# Power_Regulators_Digital_1.net
KiCad netlist of a schematic drawn in Altium Designer
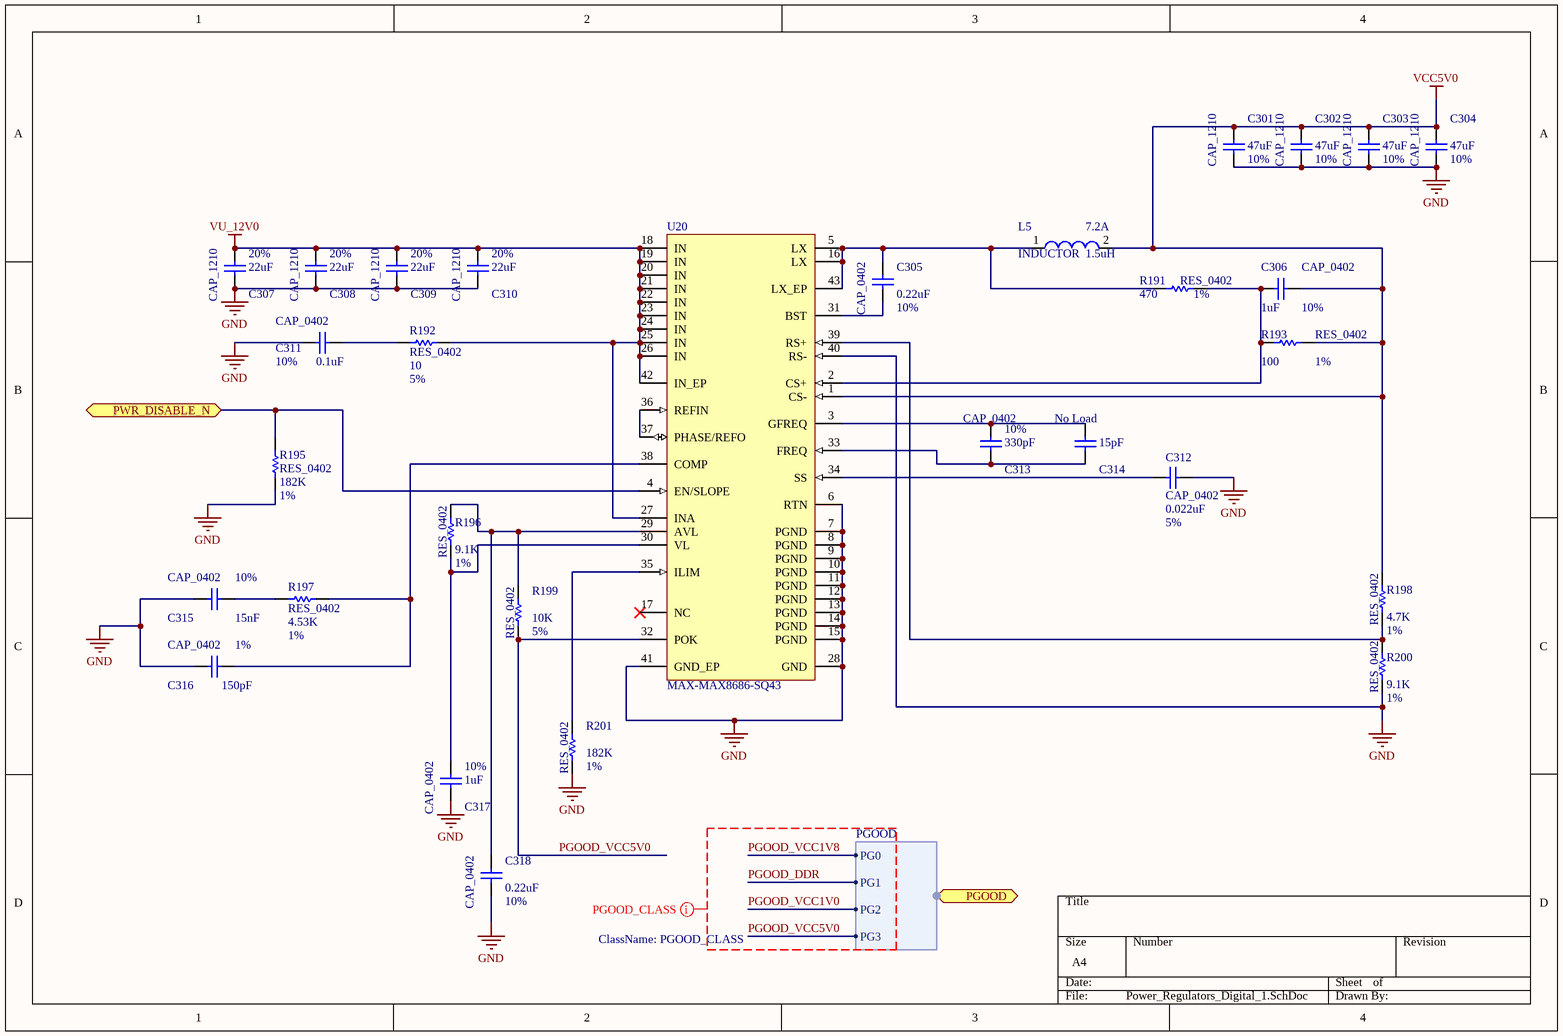
[diagram p0: Power_Regulators_Digital_1.SchDoc]

(export (version "E")
  (design (tool "Eeschema 10.0.6"))
  (components
    (comp (ref "C301")
      (value "CAP_1210")
      (footprint "CAPC1210(3225)100_N")
      (description "47uF, ceramic, 10% 10V X7R, 1210")
      (fields
        (field (name "ALTIUM_VALUE") "47uF")
        (field (name "TOLERANCE") "10%")
        (field (name "PART NUMBER") "GRM32ER71A476KE15L")
        (field (name "MANUFACTURER") "Murata Electronics North America")
      )
      (libsource (lib "COMRAD_Database") (part "CAP_1210"))
    )
    (comp (ref "C302")
      (value "CAP_1210")
      (footprint "CAPC1210(3225)100_N")
      (description "47uF, ceramic, 10% 10V X7R, 1210")
      (fields
        (field (name "ALTIUM_VALUE") "47uF")
        (field (name "TOLERANCE") "10%")
        (field (name "PART NUMBER") "GRM32ER71A476KE15L")
        (field (name "MANUFACTURER") "Murata Electronics North America")
      )
      (libsource (lib "COMRAD_Database") (part "CAP_1210"))
    )
    (comp (ref "C303")
      (value "CAP_1210")
      (footprint "CAPC1210(3225)100_N")
      (description "47uF, ceramic, 10% 10V X7R, 1210")
      (fields
        (field (name "ALTIUM_VALUE") "47uF")
        (field (name "TOLERANCE") "10%")
        (field (name "PART NUMBER") "GRM32ER71A476KE15L")
        (field (name "MANUFACTURER") "Murata Electronics North America")
      )
      (libsource (lib "COMRAD_Database") (part "CAP_1210"))
    )
    (comp (ref "C304")
      (value "CAP_1210")
      (footprint "CAPC1210(3225)100_N")
      (description "47uF, ceramic, 10% 10V X7R, 1210")
      (fields
        (field (name "ALTIUM_VALUE") "47uF")
        (field (name "TOLERANCE") "10%")
        (field (name "PART NUMBER") "GRM32ER71A476KE15L")
        (field (name "MANUFACTURER") "Murata Electronics North America")
      )
      (libsource (lib "COMRAD_Database") (part "CAP_1210"))
    )
    (comp (ref "C305")
      (value "CAP_0402")
      (footprint "CAPC0402(1005)60_N")
      (description "0.22uF, ceramic, 10%, 6.3V X5R, 0402")
      (fields
        (field (name "ALTIUM_VALUE") "0.22uF")
        (field (name "TOLERANCE") "10%")
        (field (name "PART NUMBER") "04026D224KAT2A")
        (field (name "MANUFACTURER") "AVX Corporation")
      )
      (libsource (lib "COMRAD_Database") (part "CAP_0402"))
    )
    (comp (ref "C306")
      (value "CAP_0402")
      (footprint "CAPC0402(1005)60_N")
      (description "1uF, ceramic, 10%, 6.3V, X5R, 0402")
      (fields
        (field (name "ALTIUM_VALUE") "1uF")
        (field (name "TOLERANCE") "10%")
        (field (name "PART NUMBER") "C1005X5R0J105K")
        (field (name "MANUFACTURER") "TDK Corporation")
      )
      (libsource (lib "COMRAD_Database") (part "CAP_0402"))
    )
    (comp (ref "C307")
      (value "CAP_1210")
      (footprint "CAPC1210(3225)100_N")
      (description "22uF, ceramic, 20% 25V X7R, 1210")
      (fields
        (field (name "ALTIUM_VALUE") "22uF")
        (field (name "TOLERANCE") "20%")
        (field (name "PART NUMBER") "C1210C226M3RACTU")
        (field (name "MANUFACTURER") "Kemet")
      )
      (libsource (lib "COMRAD_Database") (part "CAP_1210"))
    )
    (comp (ref "C308")
      (value "CAP_1210")
      (footprint "CAPC1210(3225)100_N")
      (description "22uF, ceramic, 20% 25V X7R, 1210")
      (fields
        (field (name "ALTIUM_VALUE") "22uF")
        (field (name "TOLERANCE") "20%")
        (field (name "PART NUMBER") "C1210C226M3RACTU")
        (field (name "MANUFACTURER") "Kemet")
      )
      (libsource (lib "COMRAD_Database") (part "CAP_1210"))
    )
    (comp (ref "C309")
      (value "CAP_1210")
      (footprint "CAPC1210(3225)100_N")
      (description "22uF, ceramic, 20% 25V X7R, 1210")
      (fields
        (field (name "ALTIUM_VALUE") "22uF")
        (field (name "TOLERANCE") "20%")
        (field (name "PART NUMBER") "C1210C226M3RACTU")
        (field (name "MANUFACTURER") "Kemet")
      )
      (libsource (lib "COMRAD_Database") (part "CAP_1210"))
    )
    (comp (ref "C310")
      (value "CAP_1210")
      (footprint "CAPC1210(3225)100_N")
      (description "22uF, ceramic, 20% 25V X7R, 1210")
      (fields
        (field (name "ALTIUM_VALUE") "22uF")
        (field (name "TOLERANCE") "20%")
        (field (name "PART NUMBER") "C1210C226M3RACTU")
        (field (name "MANUFACTURER") "Kemet")
      )
      (libsource (lib "COMRAD_Database") (part "CAP_1210"))
    )
    (comp (ref "C311")
      (value "CAP_0402")
      (footprint "CAPC0402(1005)60_N")
      (description "0.1uF, ceramic, 10%, 25V, X5R, 0402")
      (fields
        (field (name "ALTIUM_VALUE") "0.1uF")
        (field (name "TOLERANCE") "10%")
        (field (name "PART NUMBER") "TMK105BJ104KV-F")
        (field (name "MANUFACTURER") "Taiyo Yuden")
      )
      (libsource (lib "COMRAD_Database") (part "CAP_0402"))
    )
    (comp (ref "C312")
      (value "CAP_0402")
      (footprint "CAPC0402(1005)60_N")
      (description "0.022uF, ceramic, 5% 16V X7R, 0402")
      (fields
        (field (name "ALTIUM_VALUE") "0.022uF")
        (field (name "TOLERANCE") "5%")
        (field (name "PART NUMBER") "0402YC223JAT2A")
        (field (name "MANUFACTURER") "AVX Corporation")
      )
      (libsource (lib "COMRAD_Database") (part "CAP_0402"))
    )
    (comp (ref "C313")
      (value "CAP_0402")
      (footprint "CAPC0402(1005)60_N")
      (description "330pF, ceramic, 10% 10V X7R, 0402")
      (fields
        (field (name "ALTIUM_VALUE") "330pF")
        (field (name "TOLERANCE") "10%")
        (field (name "PART NUMBER") "0402ZC331KAT2A")
        (field (name "MANUFACTURER") "AVX Corporation")
      )
      (libsource (lib "COMRAD_Database") (part "CAP_0402"))
    )
    (comp (ref "C314")
      (value "15pF")
      (footprint "CAPC0201(0603)33_N:CAPC0201(0603)33_N")
      (description "Generic Capacitor")
      (fields
        (field (name "PART NUMBER") "No Load_15pF")
        (field (name "MANUFACTURER") "No Load")
        (field (name "Comment") "CAP_0201")
      )
      (libsource (lib "COMRAD_Database") (part "CAP_0201"))
    )
    (comp (ref "C315")
      (value "CAP_0402")
      (footprint "CAPC0402(1005)60_N")
      (description "0.015uF, ceramic, 10% 6.3V X5R, 0402")
      (fields
        (field (name "ALTIUM_VALUE") "15nF")
        (field (name "TOLERANCE") "10%")
        (field (name "PART NUMBER") "C0402C153K9PACTU")
        (field (name "MANUFACTURER") "Kemet")
      )
      (libsource (lib "COMRAD_Database") (part "CAP_0402"))
    )
    (comp (ref "C316")
      (value "CAP_0402")
      (footprint "CAPC0402(1005)60_N")
      (description "150pF, ceramic, 1% 50V NP0, 0402")
      (fields
        (field (name "ALTIUM_VALUE") "150pF")
        (field (name "TOLERANCE") "1%")
        (field (name "PART NUMBER") "C1005C0G1H151F")
        (field (name "MANUFACTURER") "TDK Corporation")
      )
      (libsource (lib "COMRAD_Database") (part "CAP_0402"))
    )
    (comp (ref "C317")
      (value "CAP_0402")
      (footprint "CAPC0402(1005)60_N")
      (description "1uF, ceramic, 10%, 6.3V, X5R, 0402")
      (fields
        (field (name "ALTIUM_VALUE") "1uF")
        (field (name "TOLERANCE") "10%")
        (field (name "PART NUMBER") "C1005X5R0J105K")
        (field (name "MANUFACTURER") "TDK Corporation")
      )
      (libsource (lib "COMRAD_Database") (part "CAP_0402"))
    )
    (comp (ref "C318")
      (value "CAP_0402")
      (footprint "CAPC0402(1005)60_N")
      (description "0.22uF, ceramic, 10%, 6.3V X5R, 0402")
      (fields
        (field (name "ALTIUM_VALUE") "0.22uF")
        (field (name "TOLERANCE") "10%")
        (field (name "PART NUMBER") "04026D224KAT2A")
        (field (name "MANUFACTURER") "AVX Corporation")
      )
      (libsource (lib "COMRAD_Database") (part "CAP_0402"))
    )
    (comp (ref "L5")
      (value "INDUCTOR")
      (footprint "Inductor_IHLP2020CZER1R5M01_2-PIN")
      (description "IHLP2020CZER1R5M01, 1.5uH 7.2A, SMD")
      (fields
        (field (name "ALTIUM_VALUE") "1.5uH")
        (field (name "CURRENT") "7.2A")
        (field (name "PART NUMBER") "IHLP2020CZER1R5M01")
        (field (name "MANUFACTURER") "Vishay/Dale")
      )
      (libsource (lib "COMRAD_Database") (part "SYM-0029-00001-1"))
    )
    (comp (ref "R191")
      (value "RES_0402")
      (footprint "RESC0402(1005)_N")
      (description "470 ohm, 1% 1/16W, 0402")
      (fields
        (field (name "ALTIUM_VALUE") "470")
        (field (name "TOLERANCE") "1%")
        (field (name "PART NUMBER") "RC0402FR-07470RL")
        (field (name "MANUFACTURER") "YAGEO")
      )
      (libsource (lib "COMRAD_Database") (part "RES_0402"))
    )
    (comp (ref "R192")
      (value "RES_0402")
      (footprint "RESC0402(1005)_N")
      (description "10 ohm, 5%, 1/16W, 0402")
      (fields
        (field (name "ALTIUM_VALUE") "10")
        (field (name "TOLERANCE") "5%")
        (field (name "PART NUMBER") "RC0402JR-0710RL")
        (field (name "MANUFACTURER") "Yageo America")
      )
      (libsource (lib "COMRAD_Database") (part "RES_0402"))
    )
    (comp (ref "R193")
      (value "RES_0402")
      (footprint "RESC0402(1005)_N")
      (description "100 ohm, 1%, 1/16W, 0402")
      (fields
        (field (name "ALTIUM_VALUE") "100")
        (field (name "TOLERANCE") "1%")
        (field (name "PART NUMBER") "MCR01MZPF1000")
        (field (name "MANUFACTURER") "ROHM")
      )
      (libsource (lib "COMRAD_Database") (part "RES_0402"))
    )
    (comp (ref "R195")
      (value "RES_0402")
      (footprint "RESC0402(1005)_N")
      (description "182K ohm, 1%, 1/16W, 0402")
      (fields
        (field (name "ALTIUM_VALUE") "182K")
        (field (name "TOLERANCE") "1%")
        (field (name "PART NUMBER") "ERJ-2RKF1823X")
        (field (name "MANUFACTURER") "Panasonic - ECG")
      )
      (libsource (lib "COMRAD_Database") (part "RES_0402"))
    )
    (comp (ref "R196")
      (value "RES_0402")
      (footprint "RESC0402(1005)_N")
      (description "9.1K ohm, 1% 1/10W, 0402")
      (fields
        (field (name "ALTIUM_VALUE") "9.1K")
        (field (name "TOLERANCE") "1%")
        (field (name "PART NUMBER") "ERJ-2RKF9101X")
        (field (name "MANUFACTURER") "Panasonic - ECG")
      )
      (libsource (lib "COMRAD_Database") (part "RES_0402"))
    )
    (comp (ref "R197")
      (value "RES_0402")
      (footprint "RESC0402(1005)_N")
      (description "4.53K ohm, 1%, 1/16W, 0402")
      (fields
        (field (name "ALTIUM_VALUE") "4.53K")
        (field (name "TOLERANCE") "1%")
        (field (name "PART NUMBER") "ERJ-2RKF4531X")
        (field (name "MANUFACTURER") "Panasonic - ECG")
      )
      (libsource (lib "COMRAD_Database") (part "RES_0402"))
    )
    (comp (ref "R198")
      (value "RES_0402")
      (footprint "RESC0402(1005)_N")
      (description "4.7K ohm, 1%, 1/16W, 0402")
      (fields
        (field (name "ALTIUM_VALUE") "4.7K")
        (field (name "TOLERANCE") "1%")
        (field (name "PART NUMBER") "RC0402FR-074K7L")
        (field (name "MANUFACTURER") "Yageo America")
      )
      (libsource (lib "COMRAD_Database") (part "RES_0402"))
    )
    (comp (ref "R199")
      (value "RES_0402")
      (footprint "RESC0402(1005)_N")
      (description "10K ohm, 5%, 1/16W, 0402")
      (fields
        (field (name "ALTIUM_VALUE") "10K")
        (field (name "TOLERANCE") "5%")
        (field (name "PART NUMBER") "RC0402JR-0710KL")
        (field (name "MANUFACTURER") "Yageo America")
      )
      (libsource (lib "COMRAD_Database") (part "RES_0402"))
    )
    (comp (ref "R200")
      (value "RES_0402")
      (footprint "RESC0402(1005)_N")
      (description "9.1K ohm, 1% 1/10W, 0402")
      (fields
        (field (name "ALTIUM_VALUE") "9.1K")
        (field (name "TOLERANCE") "1%")
        (field (name "PART NUMBER") "ERJ-2RKF9101X")
        (field (name "MANUFACTURER") "Panasonic - ECG")
      )
      (libsource (lib "COMRAD_Database") (part "RES_0402"))
    )
    (comp (ref "R201")
      (value "RES_0402")
      (footprint "RESC0402(1005)_N")
      (description "182K ohm, 1%, 1/16W, 0402")
      (fields
        (field (name "ALTIUM_VALUE") "182K")
        (field (name "TOLERANCE") "1%")
        (field (name "PART NUMBER") "ERJ-2RKF1823X")
        (field (name "MANUFACTURER") "Panasonic - ECG")
      )
      (libsource (lib "COMRAD_Database") (part "RES_0402"))
    )
    (comp (ref "U20")
      (value "MAX-MAX8686-SQ43")
      (footprint "MAX_MAX8686_T4066M+1_N")
      (description "MAX8686ETL+, Buck Sync ADJ 25A, TQFP40-EP")
      (fields
        (field (name "PART NUMBER") "MAX8686ETL+")
        (field (name "MANUFACTURER") "Maxim Integrated Products")
      )
      (libsource (lib "COMRAD_Database") (part "MAX-MAX8686-SQ43"))
    )
  )
  (nets
    (net (code "5") (name "/PGOOD_VCC5V0") (class "Default")
      (node (ref "R199") (pin "1") (pinfunction "1_1") (pintype "passive"))
      (node (ref "U20") (pin "32") (pinfunction "POK_32") (pintype "passive"))
    )
    (net (code "6") (name "/PWR_DISABLE_N") (class "Default")
      (node (ref "R195") (pin "2") (pinfunction "2_2") (pintype "passive"))
      (node (ref "U20") (pin "4") (pinfunction "EN/SLOPE_4") (pintype "input"))
    )
    (net (code "8") (name "GND") (class "Default")
      (node (ref "C301") (pin "1") (pinfunction "1_1") (pintype "passive"))
      (node (ref "C302") (pin "1") (pinfunction "1_1") (pintype "passive"))
      (node (ref "C303") (pin "1") (pinfunction "1_1") (pintype "passive"))
      (node (ref "C304") (pin "1") (pinfunction "1_1") (pintype "passive"))
      (node (ref "C307") (pin "1") (pinfunction "1_1") (pintype "passive"))
      (node (ref "C308") (pin "1") (pinfunction "1_1") (pintype "passive"))
      (node (ref "C309") (pin "1") (pinfunction "1_1") (pintype "passive"))
      (node (ref "C310") (pin "1") (pinfunction "1_1") (pintype "passive"))
      (node (ref "C311") (pin "2") (pinfunction "2_2") (pintype "passive"))
      (node (ref "C312") (pin "2") (pinfunction "2_2") (pintype "passive"))
      (node (ref "C315") (pin "1") (pinfunction "1_1") (pintype "passive"))
      (node (ref "C316") (pin "2") (pinfunction "2_2") (pintype "passive"))
      (node (ref "C317") (pin "1") (pinfunction "1_1") (pintype "passive"))
      (node (ref "C318") (pin "1") (pinfunction "1_1") (pintype "passive"))
      (node (ref "R195") (pin "1") (pinfunction "1_1") (pintype "passive"))
      (node (ref "R200") (pin "1") (pinfunction "1_1") (pintype "passive"))
      (node (ref "R201") (pin "1") (pinfunction "1_1") (pintype "passive"))
      (node (ref "U20") (pin "10") (pinfunction "PGND_10") (pintype "power_in"))
      (node (ref "U20") (pin "11") (pinfunction "PGND_11") (pintype "power_in"))
      (node (ref "U20") (pin "12") (pinfunction "PGND_12") (pintype "power_in"))
      (node (ref "U20") (pin "13") (pinfunction "PGND_13") (pintype "power_in"))
      (node (ref "U20") (pin "14") (pinfunction "PGND_14") (pintype "power_in"))
      (node (ref "U20") (pin "15") (pinfunction "PGND_15") (pintype "power_in"))
      (node (ref "U20") (pin "28") (pinfunction "GND_28") (pintype "power_in"))
      (node (ref "U20") (pin "40") (pinfunction "RS-_40") (pintype "input"))
      (node (ref "U20") (pin "41") (pinfunction "GND_EP_41") (pintype "power_in"))
      (node (ref "U20") (pin "6") (pinfunction "RTN_6") (pintype "power_in"))
      (node (ref "U20") (pin "7") (pinfunction "PGND_7") (pintype "power_in"))
      (node (ref "U20") (pin "8") (pinfunction "PGND_8") (pintype "power_in"))
      (node (ref "U20") (pin "9") (pinfunction "PGND_9") (pintype "power_in"))
    )
    (net (code "9") (name "Net-(C311-Pad1)") (class "Default")
      (node (ref "C311") (pin "1") (pinfunction "1_1") (pintype "passive"))
      (node (ref "R192") (pin "2") (pinfunction "2_2") (pintype "passive"))
    )
    (net (code "10") (name "Net-(C315-Pad2)") (class "Default")
      (node (ref "C315") (pin "2") (pinfunction "2_2") (pintype "passive"))
      (node (ref "R197") (pin "1") (pinfunction "1_1") (pintype "passive"))
    )
    (net (code "11") (name "Net-(U20-AVL)") (class "Default")
      (node (ref "C318") (pin "2") (pinfunction "2_2") (pintype "passive"))
      (node (ref "R196") (pin "2") (pinfunction "2_2") (pintype "passive"))
      (node (ref "R199") (pin "2") (pinfunction "2_2") (pintype "passive"))
      (node (ref "U20") (pin "29") (pinfunction "AVL_29") (pintype "power_in"))
    )
    (net (code "12") (name "Net-(U20-BST)") (class "Default")
      (node (ref "C305") (pin "1") (pinfunction "1_1") (pintype "passive"))
      (node (ref "U20") (pin "31") (pinfunction "BST_31") (pintype "passive"))
    )
    (net (code "13") (name "Net-(U20-COMP)") (class "Default")
      (node (ref "C316") (pin "1") (pinfunction "1_1") (pintype "passive"))
      (node (ref "R197") (pin "2") (pinfunction "2_2") (pintype "passive"))
      (node (ref "U20") (pin "38") (pinfunction "COMP_38") (pintype "passive"))
    )
    (net (code "14") (name "Net-(U20-CS+)") (class "Default")
      (node (ref "C306") (pin "1") (pinfunction "1_1") (pintype "passive"))
      (node (ref "R191") (pin "2") (pinfunction "2_2") (pintype "passive"))
      (node (ref "R193") (pin "1") (pinfunction "1_1") (pintype "passive"))
      (node (ref "U20") (pin "2") (pinfunction "CS+_2") (pintype "input"))
    )
    (net (code "15") (name "Net-(U20-FREQ)") (class "Default")
      (node (ref "C313") (pin "1") (pinfunction "1_1") (pintype "passive"))
      (node (ref "C314") (pin "1") (pinfunction "1_1") (pintype "passive"))
      (node (ref "U20") (pin "33") (pinfunction "FREQ_33") (pintype "input"))
    )
    (net (code "16") (name "Net-(U20-GFREQ)") (class "Default")
      (node (ref "C313") (pin "2") (pinfunction "2_2") (pintype "passive"))
      (node (ref "C314") (pin "2") (pinfunction "2_2") (pintype "passive"))
      (node (ref "U20") (pin "3") (pinfunction "GFREQ_3") (pintype "passive"))
    )
    (net (code "17") (name "Net-(U20-ILIM)") (class "Default")
      (node (ref "R201") (pin "2") (pinfunction "2_2") (pintype "passive"))
      (node (ref "U20") (pin "35") (pinfunction "ILIM_35") (pintype "input"))
    )
    (net (code "18") (name "Net-(U20-LX_EP)") (class "Default")
      (node (ref "C305") (pin "2") (pinfunction "2_2") (pintype "passive"))
      (node (ref "L5") (pin "1") (pinfunction "1_1") (pintype "passive"))
      (node (ref "R191") (pin "1") (pinfunction "1_1") (pintype "passive"))
      (node (ref "U20") (pin "16") (pinfunction "LX_16") (pintype "passive"))
      (node (ref "U20") (pin "43") (pinfunction "LX_EP_43") (pintype "passive"))
      (node (ref "U20") (pin "5") (pinfunction "LX_5") (pintype "passive"))
    )
    (net (code "19") (name "Net-(U20-PHASE{slash}REFO)") (class "Default")
      (node (ref "U20") (pin "36") (pinfunction "REFIN_36") (pintype "input"))
      (node (ref "U20") (pin "37") (pinfunction "PHASE/REFO_37") (pintype "bidirectional"))
    )
    (net (code "20") (name "Net-(U20-RS+)") (class "Default")
      (node (ref "R198") (pin "1") (pinfunction "1_1") (pintype "passive"))
      (node (ref "R200") (pin "2") (pinfunction "2_2") (pintype "passive"))
      (node (ref "U20") (pin "39") (pinfunction "RS+_39") (pintype "input"))
    )
    (net (code "21") (name "Net-(U20-SS)") (class "Default")
      (node (ref "C312") (pin "1") (pinfunction "1_1") (pintype "passive"))
      (node (ref "U20") (pin "34") (pinfunction "SS_34") (pintype "input"))
    )
    (net (code "22") (name "Net-(U20-VL)") (class "Default")
      (node (ref "C317") (pin "2") (pinfunction "2_2") (pintype "passive"))
      (node (ref "R196") (pin "1") (pinfunction "1_1") (pintype "passive"))
      (node (ref "U20") (pin "30") (pinfunction "VL_30") (pintype "power_in"))
    )
    (net (code "23") (name "VCC5V0") (class "Default")
      (node (ref "C301") (pin "2") (pinfunction "2_2") (pintype "passive"))
      (node (ref "C302") (pin "2") (pinfunction "2_2") (pintype "passive"))
      (node (ref "C303") (pin "2") (pinfunction "2_2") (pintype "passive"))
      (node (ref "C304") (pin "2") (pinfunction "2_2") (pintype "passive"))
      (node (ref "C306") (pin "2") (pinfunction "2_2") (pintype "passive"))
      (node (ref "L5") (pin "2") (pinfunction "2_2") (pintype "passive"))
      (node (ref "R193") (pin "2") (pinfunction "2_2") (pintype "passive"))
      (node (ref "R198") (pin "2") (pinfunction "2_2") (pintype "passive"))
      (node (ref "U20") (pin "1") (pinfunction "CS-_1") (pintype "input"))
    )
    (net (code "24") (name "VU_12V0") (class "Default")
      (node (ref "C307") (pin "2") (pinfunction "2_2") (pintype "passive"))
      (node (ref "C308") (pin "2") (pinfunction "2_2") (pintype "passive"))
      (node (ref "C309") (pin "2") (pinfunction "2_2") (pintype "passive"))
      (node (ref "C310") (pin "2") (pinfunction "2_2") (pintype "passive"))
      (node (ref "R192") (pin "1") (pinfunction "1_1") (pintype "passive"))
      (node (ref "U20") (pin "18") (pinfunction "IN_18") (pintype "power_in"))
      (node (ref "U20") (pin "19") (pinfunction "IN_19") (pintype "power_in"))
      (node (ref "U20") (pin "20") (pinfunction "IN_20") (pintype "power_in"))
      (node (ref "U20") (pin "21") (pinfunction "IN_21") (pintype "power_in"))
      (node (ref "U20") (pin "22") (pinfunction "IN_22") (pintype "power_in"))
      (node (ref "U20") (pin "23") (pinfunction "IN_23") (pintype "power_in"))
      (node (ref "U20") (pin "24") (pinfunction "IN_24") (pintype "power_in"))
      (node (ref "U20") (pin "25") (pinfunction "IN_25") (pintype "power_in"))
      (node (ref "U20") (pin "26") (pinfunction "IN_26") (pintype "power_in"))
      (node (ref "U20") (pin "27") (pinfunction "INA_27") (pintype "power_in"))
      (node (ref "U20") (pin "42") (pinfunction "IN_EP_42") (pintype "passive"))
    )
    (net (code "25") (name "unconnected-(U20-NC-Pad17)") (class "Default")
      (node (ref "U20") (pin "17") (pinfunction "NC_17") (pintype "passive+no_connect"))
    )
  )
)
